# untitled.net
KiCad netlist of a schematic drawn in EAGLE
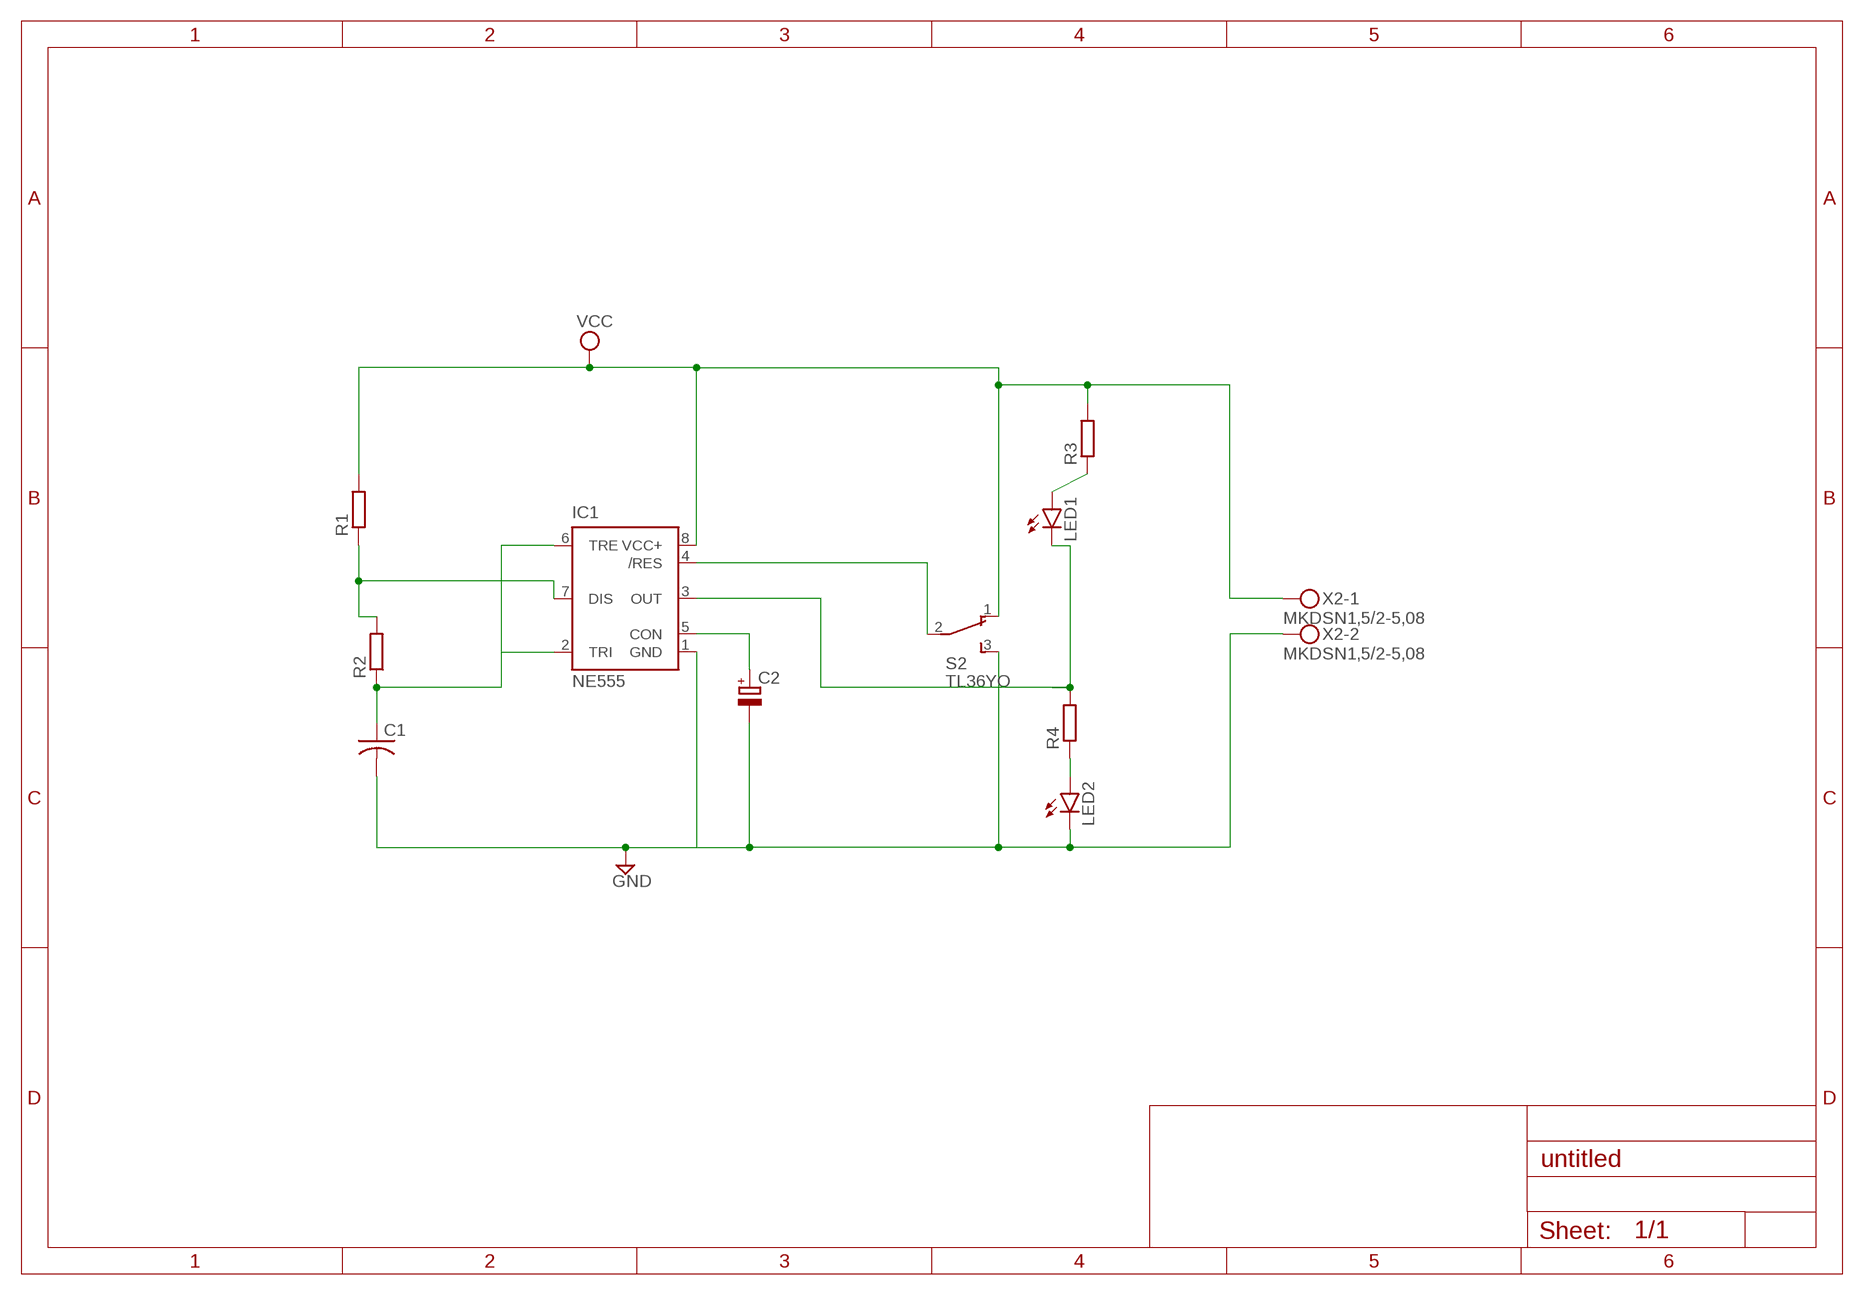
[diagram p0: schematic, sheet 1]

(export (version "E")
  (design (tool "Eeschema 10.0.6"))
  (components
    (comp (ref "C1")
      (value "C-US025-025X050")
      (footprint "eagle-import:C025-025X050")
      (libsource (lib "eagle-import") (part "C-US025-025X050"))
    )
    (comp (ref "C2")
      (value "CPOL-EUE3.5-8")
      (footprint "eagle-import:E3,5-8")
      (libsource (lib "eagle-import") (part "CPOL-EUE3.5-8"))
    )
    (comp (ref "IC1")
      (value "NE555")
      (footprint "eagle-import:DIL-08")
      (fields (field (name "MF") "Arrow Electronics") (field (name "MPN") "NE555N"))
      (libsource (lib "eagle-import") (part "NE555"))
    )
    (comp (ref "LED1")
      (value "LED5MM")
      (footprint "eagle-import:LED5MM")
      (libsource (lib "eagle-import") (part "LED5MM"))
    )
    (comp (ref "LED2")
      (value "LED5MM")
      (footprint "eagle-import:LED5MM")
      (libsource (lib "eagle-import") (part "LED5MM"))
    )
    (comp (ref "R1")
      (value "R-EU_0309/12")
      (footprint "eagle-import:0309_12")
      (libsource (lib "eagle-import") (part "R-EU_0309/12"))
    )
    (comp (ref "R2")
      (value "R-EU_0309/12")
      (footprint "eagle-import:0309_12")
      (libsource (lib "eagle-import") (part "R-EU_0309/12"))
    )
    (comp (ref "R3")
      (value "R-EU_0309/12")
      (footprint "eagle-import:0309_12")
      (libsource (lib "eagle-import") (part "R-EU_0309/12"))
    )
    (comp (ref "R4")
      (value "R-EU_0309/12")
      (footprint "eagle-import:0309_12")
      (libsource (lib "eagle-import") (part "R-EU_0309/12"))
    )
    (comp (ref "S2")
      (value "TL36YO")
      (footprint "eagle-import:TL3XYO")
      (libsource (lib "eagle-import") (part "TL36YO"))
    )
    (comp (ref "X2")
      (value "MKDSN1,5/2-5,08")
      (footprint "eagle-import:MKDSN1,5_2-5,08")
      (libsource (lib "eagle-import") (part "MKDSN1,5/2-5,08"))
    )
  )
  (nets
    (net (code "1") (name "GND") (class "Default")
      (node (ref "C1") (pin "2") (pinfunction "2_2") (pintype "passive"))
      (node (ref "C2") (pin "-") (pinfunction "-_-") (pintype "passive"))
      (node (ref "IC1") (pin "1") (pinfunction "GND_1") (pintype "power_in"))
      (node (ref "LED2") (pin "K") (pinfunction "C_K") (pintype "passive"))
      (node (ref "S2") (pin "3") (pinfunction "S_3") (pintype "passive"))
      (node (ref "X2") (pin "2") (pinfunction "KL_2") (pintype "passive"))
    )
    (net (code "2") (name "Net-(IC1-CON)") (class "Default")
      (node (ref "C2") (pin "+") (pinfunction "+_+") (pintype "passive"))
      (node (ref "IC1") (pin "5") (pinfunction "CON_5") (pintype "input"))
    )
    (net (code "3") (name "Net-(IC1-DIS)") (class "Default")
      (node (ref "IC1") (pin "7") (pinfunction "DIS_7") (pintype "input"))
      (node (ref "R1") (pin "1") (pinfunction "1_1") (pintype "passive"))
      (node (ref "R2") (pin "2") (pinfunction "2_2") (pintype "passive"))
    )
    (net (code "4") (name "Net-(IC1-OUT)") (class "Default")
      (node (ref "IC1") (pin "3") (pinfunction "OUT_3") (pintype "output"))
      (node (ref "LED1") (pin "K") (pinfunction "C_K") (pintype "passive"))
      (node (ref "R4") (pin "2") (pinfunction "2_2") (pintype "passive"))
    )
    (net (code "5") (name "Net-(IC1-TRE)") (class "Default")
      (node (ref "C1") (pin "1") (pinfunction "1_1") (pintype "passive"))
      (node (ref "IC1") (pin "2") (pinfunction "TRI_2") (pintype "input"))
      (node (ref "IC1") (pin "6") (pinfunction "TRE_6") (pintype "input"))
      (node (ref "R2") (pin "1") (pinfunction "1_1") (pintype "passive"))
    )
    (net (code "6") (name "Net-(IC1-{slash}RES)") (class "Default")
      (node (ref "IC1") (pin "4") (pinfunction "/RES_4") (pintype "input"))
      (node (ref "S2") (pin "2") (pinfunction "P_2") (pintype "passive"))
    )
    (net (code "7") (name "Net-(LED1-PadA)") (class "Default")
      (node (ref "LED1") (pin "A") (pinfunction "A_A") (pintype "passive"))
      (node (ref "R3") (pin "1") (pinfunction "1_1") (pintype "passive"))
    )
    (net (code "8") (name "Net-(LED2-PadA)") (class "Default")
      (node (ref "LED2") (pin "A") (pinfunction "A_A") (pintype "passive"))
      (node (ref "R4") (pin "1") (pinfunction "1_1") (pintype "passive"))
    )
    (net (code "9") (name "VCC") (class "Default")
      (node (ref "IC1") (pin "8") (pinfunction "VCC+_8") (pintype "power_in"))
      (node (ref "R1") (pin "2") (pinfunction "2_2") (pintype "passive"))
      (node (ref "R3") (pin "2") (pinfunction "2_2") (pintype "passive"))
      (node (ref "S2") (pin "1") (pinfunction "O_1") (pintype "passive"))
      (node (ref "X2") (pin "1") (pinfunction "KL_1") (pintype "passive"))
    )
  )
)
